# Sheet4.net
KiCad netlist of a schematic drawn in Altium Designer
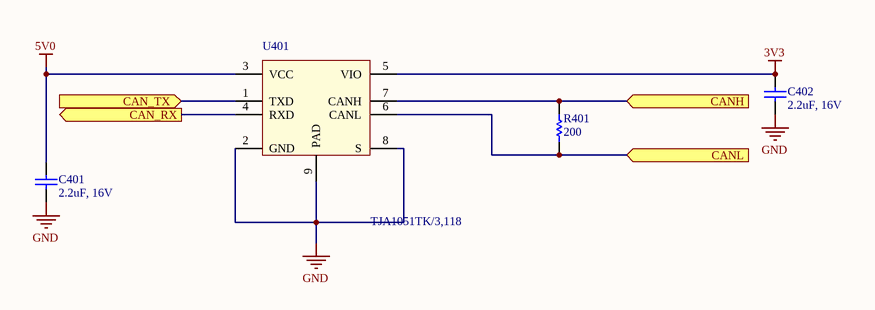
[diagram p0: Sheet4.SchDoc]

(export (version "E")
  (design (tool "Eeschema 10.0.6"))
  (components
    (comp (ref "C401")
      (value "2.2uF, 16V")
      (footprint "SMD-0603 Capacitor")
      (description "CAP 2.2u, 16V, 0603")
      (fields
        (field (name "MANUFACTURER PART NUMBER") "C1608X5R1C225M")
        (field (name "MANUFACTURER") "TDK Corporation")
      )
      (libsource (lib "Master Data Link") (part "CAP"))
    )
    (comp (ref "C402")
      (value "2.2uF, 16V")
      (footprint "SMD-0603 Capacitor")
      (description "CAP 2.2u, 16V, 0603")
      (fields
        (field (name "MANUFACTURER PART NUMBER") "C1608X5R1C225M")
        (field (name "MANUFACTURER") "TDK Corporation")
      )
      (libsource (lib "Master Data Link") (part "CAP"))
    )
    (comp (ref "R401")
      (value "200")
      (footprint "SMD-0603 Resistor")
      (description "RES SMD 200 OHM 1% 1/10W 0603")
      (fields
        (field (name "MANUFACTURER PART NUMBER") "ERJ-3EKF2000V")
        (field (name "MANUFACTURER") "Panasonic Electronic Components")
      )
      (libsource (lib "Master Data Link") (part "RES"))
    )
    (comp (ref "U401")
      (value "CAN_TRANS_1")
      (footprint "HVSON8")
      (description "IC CAN TRANSEIVER HS 8HVSON")
      (fields
        (field (name "MANUFACTURER PART NUMBER") "TJA1051TK/3,118")
        (field (name "MANUFACTURER") "NXP USA Inc.")
      )
      (libsource (lib "Master Data Link") (part "CAN_TRANS_1"))
    )
  )
  (nets
    (net (code "1") (name "/CANH") (class "Default")
      (node (ref "R401") (pin "2") (pinfunction "2_2") (pintype "passive"))
      (node (ref "U401") (pin "7") (pinfunction "CANH_7") (pintype "passive"))
    )
    (net (code "2") (name "/CANL") (class "Default")
      (node (ref "R401") (pin "1") (pinfunction "1_1") (pintype "passive"))
      (node (ref "U401") (pin "6") (pinfunction "CANL_6") (pintype "passive"))
    )
    (net (code "3") (name "/CAN_RX") (class "Default")
      (node (ref "U401") (pin "4") (pinfunction "RXD_4") (pintype "passive"))
    )
    (net (code "4") (name "/CAN_TX") (class "Default")
      (node (ref "U401") (pin "1") (pinfunction "TXD_1") (pintype "passive"))
    )
    (net (code "5") (name "3V3") (class "Default")
      (node (ref "C402") (pin "2") (pinfunction "2_2") (pintype "passive"))
      (node (ref "U401") (pin "5") (pinfunction "VIO_5") (pintype "passive"))
    )
    (net (code "6") (name "5V0") (class "Default")
      (node (ref "C401") (pin "2") (pinfunction "2_2") (pintype "passive"))
      (node (ref "U401") (pin "3") (pinfunction "VCC_3") (pintype "passive"))
    )
    (net (code "7") (name "GND") (class "Default")
      (node (ref "C401") (pin "1") (pinfunction "1_1") (pintype "passive"))
      (node (ref "C402") (pin "1") (pinfunction "1_1") (pintype "passive"))
      (node (ref "U401") (pin "2") (pinfunction "GND_2") (pintype "passive"))
      (node (ref "U401") (pin "8") (pinfunction "S_8") (pintype "passive"))
      (node (ref "U401") (pin "9") (pinfunction "PAD_9") (pintype "passive"))
    )
  )
)
